# schema_final.net
KiCad netlist of a schematic drawn in EAGLE
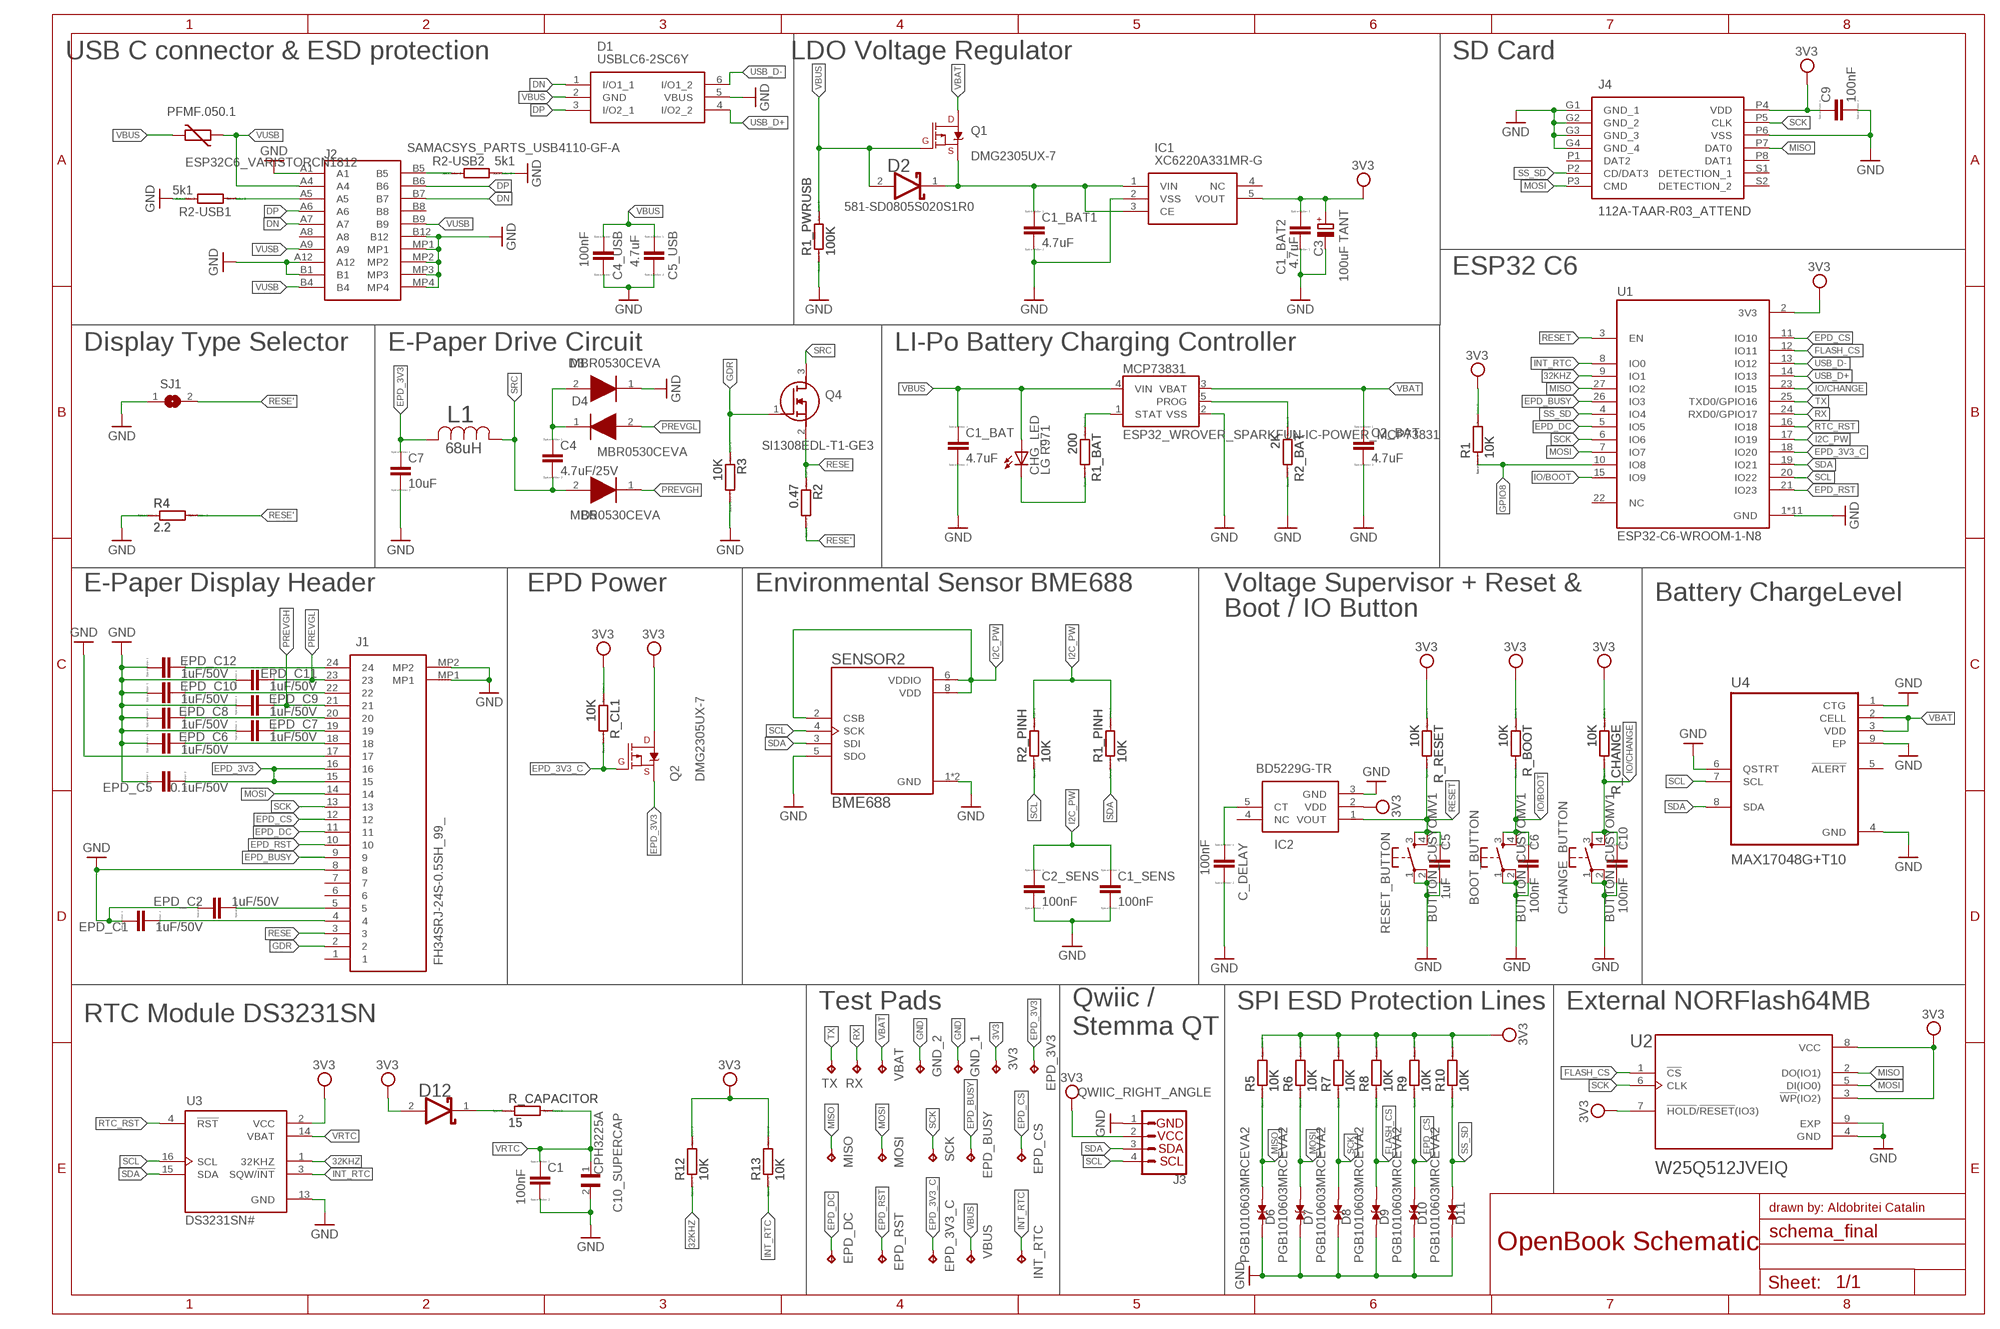
[diagram p0: schematic, sheet 1]

(export (version "E")
  (design (tool "Eeschema 10.0.6"))
  (components
    (comp (ref "3V3")
      (value "TP")
      (footprint "eagle-import:TP20R")
      (libsource (lib "eagle-import") (part "TP"))
    )
    (comp (ref "BOOT_BUTTON")
      (value "BUTTON_CUSYOMV1")
      (footprint "eagle-import:MYBUTTON")
      (libsource (lib "eagle-import") (part "BUTTON_CUSYOMV1"))
    )
    (comp (ref "C1")
      (value "100nF")
      (footprint "eagle-import:EAGLE-LTSPICE_C0402")
      (libsource (lib "eagle-import") (part "EAGLE-LTSPICE_C"))
    )
    (comp (ref "C1_BAT")
      (value "4.7uF")
      (footprint "eagle-import:EAGLE-LTSPICE_C0402")
      (libsource (lib "eagle-import") (part "EAGLE-LTSPICE_C"))
    )
    (comp (ref "C1_BAT1")
      (value "4.7uF")
      (footprint "eagle-import:EAGLE-LTSPICE_C0402")
      (libsource (lib "eagle-import") (part "EAGLE-LTSPICE_C"))
    )
    (comp (ref "C1_BAT2")
      (value "4.7uF")
      (footprint "eagle-import:EAGLE-LTSPICE_C0402")
      (libsource (lib "eagle-import") (part "EAGLE-LTSPICE_C"))
    )
    (comp (ref "C1_SENS")
      (value "100nF")
      (footprint "eagle-import:EAGLE-LTSPICE_C0402")
      (libsource (lib "eagle-import") (part "EAGLE-LTSPICE_C"))
    )
    (comp (ref "C2_BAT")
      (value "4.7uF")
      (footprint "eagle-import:EAGLE-LTSPICE_C0402")
      (libsource (lib "eagle-import") (part "EAGLE-LTSPICE_C"))
    )
    (comp (ref "C2_SENS")
      (value "100nF")
      (footprint "eagle-import:EAGLE-LTSPICE_C0402")
      (libsource (lib "eagle-import") (part "EAGLE-LTSPICE_C"))
    )
    (comp (ref "C3")
      (value "100uF TANT")
      (footprint "eagle-import:RCL_CT3528")
      (libsource (lib "eagle-import") (part "RCL_CPOL-EUCT3528"))
    )
    (comp (ref "C4")
      (value "4.7uF/25V")
      (footprint "eagle-import:EAGLE-LTSPICE_C0402")
      (libsource (lib "eagle-import") (part "EAGLE-LTSPICE_C"))
    )
    (comp (ref "C4_USB")
      (value "100nF")
      (footprint "eagle-import:EAGLE-LTSPICE_C0402")
      (libsource (lib "eagle-import") (part "EAGLE-LTSPICE_C"))
    )
    (comp (ref "C5")
      (value "1uF")
      (footprint "eagle-import:EAGLE-LTSPICE_C0402")
      (libsource (lib "eagle-import") (part "EAGLE-LTSPICE_C"))
    )
    (comp (ref "C5_USB")
      (value "4.7uF")
      (footprint "eagle-import:EAGLE-LTSPICE_C0402")
      (libsource (lib "eagle-import") (part "EAGLE-LTSPICE_C"))
    )
    (comp (ref "C6")
      (value "100nF")
      (footprint "eagle-import:EAGLE-LTSPICE_C0402")
      (libsource (lib "eagle-import") (part "EAGLE-LTSPICE_C"))
    )
    (comp (ref "C7")
      (value "10uF")
      (footprint "eagle-import:EAGLE-LTSPICE_C0402")
      (libsource (lib "eagle-import") (part "EAGLE-LTSPICE_C"))
    )
    (comp (ref "C9")
      (value "100nF")
      (footprint "eagle-import:EAGLE-LTSPICE_C0402")
      (libsource (lib "eagle-import") (part "EAGLE-LTSPICE_C"))
    )
    (comp (ref "C10")
      (value "100nF")
      (footprint "eagle-import:EAGLE-LTSPICE_C0402")
      (libsource (lib "eagle-import") (part "EAGLE-LTSPICE_C"))
    )
    (comp (ref "C10_SUPERCAP")
      (value "CPH3225A")
      (footprint "eagle-import:CAPCP3225X100N")
      (fields (field (name "MF") "Seiko Instruments"))
      (libsource (lib "eagle-import") (part "CPH3225A"))
    )
    (comp (ref "CHANGE_BUTTON")
      (value "BUTTON_CUSYOMV1")
      (footprint "eagle-import:MYBUTTON")
      (libsource (lib "eagle-import") (part "BUTTON_CUSYOMV1"))
    )
    (comp (ref "CHG_LED")
      (value "LG R971")
      (footprint "eagle-import:ADAFRUIT_CHIP-LED0603")
      (libsource (lib "eagle-import") (part "ADAFRUIT_LEDCHIP-LED0603"))
    )
    (comp (ref "C_DELAY")
      (value "100nF")
      (footprint "eagle-import:EAGLE-LTSPICE_C0402")
      (libsource (lib "eagle-import") (part "EAGLE-LTSPICE_C"))
    )
    (comp (ref "D1")
      (value "USBLC6-2SC6Y")
      (footprint "eagle-import:SOT95P280X145-6N")
      (fields (field (name "MF") "STMicroelectronics"))
      (libsource (lib "eagle-import") (part "USBLC6-2SC6Y"))
    )
    (comp (ref "D2")
      (value "ESP32_WROVER_AVX---SD0805S020S1R0_AVX_SD0805S020S1R0_0_0AVX_SD0805S020S1R0_0_0")
      (footprint "eagle-import:ESP32_WROVER_AVX---SD0805S020S1R0_AVX_SD0805S020S1R0_0")
      (fields
        (field (name "DIGIKEY_PART_NUMBER") "478-7800-1-ND")
        (field (name "MF") "AVX")
        (field (name "MOUSER_PART_NUMBER") "581-SD0805S020S1R0")
      )
      (libsource (lib "eagle-import") (part "ESP32_WROVER_AVX---SD0805S020S1R0_AVX_SD0805S020S1R0_0_0AVX_SD0805S020S1R0_0_0"))
    )
    (comp (ref "D3")
      (value "MBR0530CEVA")
      (footprint "eagle-import:SOD3716X135N")
      (libsource (lib "eagle-import") (part "MBR0530CEVA"))
    )
    (comp (ref "D4")
      (value "MBR0530CEVA")
      (footprint "eagle-import:SOD3716X135N")
      (libsource (lib "eagle-import") (part "MBR0530CEVA"))
    )
    (comp (ref "D5")
      (value "MBR0530CEVA")
      (footprint "eagle-import:SOD3716X135N")
      (libsource (lib "eagle-import") (part "MBR0530CEVA"))
    )
    (comp (ref "D6")
      (value "PGB1010603MRCEVA2")
      (footprint "eagle-import:DIOC1608X36N")
      (libsource (lib "eagle-import") (part "PGB1010603MRCEVA2"))
    )
    (comp (ref "D7")
      (value "PGB1010603MRCEVA2")
      (footprint "eagle-import:DIOC1608X36N")
      (libsource (lib "eagle-import") (part "PGB1010603MRCEVA2"))
    )
    (comp (ref "D8")
      (value "PGB1010603MRCEVA2")
      (footprint "eagle-import:DIOC1608X36N")
      (libsource (lib "eagle-import") (part "PGB1010603MRCEVA2"))
    )
    (comp (ref "D9")
      (value "PGB1010603MRCEVA2")
      (footprint "eagle-import:DIOC1608X36N")
      (libsource (lib "eagle-import") (part "PGB1010603MRCEVA2"))
    )
    (comp (ref "D10")
      (value "PGB1010603MRCEVA2")
      (footprint "eagle-import:DIOC1608X36N")
      (libsource (lib "eagle-import") (part "PGB1010603MRCEVA2"))
    )
    (comp (ref "D11")
      (value "PGB1010603MRCEVA2")
      (footprint "eagle-import:DIOC1608X36N")
      (libsource (lib "eagle-import") (part "PGB1010603MRCEVA2"))
    )
    (comp (ref "D12")
      (value "ESP32_WROVER_AVX---SD0805S020S1R0_AVX_SD0805S020S1R0_0_0AVX_SD0805S020S1R0_0_0")
      (footprint "eagle-import:ESP32_WROVER_AVX---SD0805S020S1R0_AVX_SD0805S020S1R0_0")
      (fields
        (field (name "DIGIKEY_PART_NUMBER") "478-7800-1-ND")
        (field (name "MF") "AVX")
        (field (name "MOUSER_PART_NUMBER") "581-SD0805S020S1R0")
      )
      (libsource (lib "eagle-import") (part "ESP32_WROVER_AVX---SD0805S020S1R0_AVX_SD0805S020S1R0_0_0AVX_SD0805S020S1R0_0_0"))
    )
    (comp (ref "EPD_3V3")
      (value "TP")
      (footprint "eagle-import:TP20R")
      (libsource (lib "eagle-import") (part "TP"))
    )
    (comp (ref "EPD_3V3_C")
      (value "TP")
      (footprint "eagle-import:TP20R")
      (libsource (lib "eagle-import") (part "TP"))
    )
    (comp (ref "EPD_BUSY")
      (value "TP")
      (footprint "eagle-import:TP20R")
      (libsource (lib "eagle-import") (part "TP"))
    )
    (comp (ref "EPD_C1")
      (value "1uF/50V")
      (footprint "eagle-import:EAGLE-LTSPICE_C0402")
      (libsource (lib "eagle-import") (part "EAGLE-LTSPICE_C"))
    )
    (comp (ref "EPD_C2")
      (value "1uF/50V")
      (footprint "eagle-import:EAGLE-LTSPICE_C0402")
      (libsource (lib "eagle-import") (part "EAGLE-LTSPICE_C"))
    )
    (comp (ref "EPD_C5")
      (value "0.1uF/50V")
      (footprint "eagle-import:EAGLE-LTSPICE_C0402")
      (libsource (lib "eagle-import") (part "EAGLE-LTSPICE_C"))
    )
    (comp (ref "EPD_C6")
      (value "1uF/50V")
      (footprint "eagle-import:EAGLE-LTSPICE_C0402")
      (libsource (lib "eagle-import") (part "EAGLE-LTSPICE_C"))
    )
    (comp (ref "EPD_C7")
      (value "1uF/50V")
      (footprint "eagle-import:EAGLE-LTSPICE_C0402")
      (libsource (lib "eagle-import") (part "EAGLE-LTSPICE_C"))
    )
    (comp (ref "EPD_C8")
      (value "1uF/50V")
      (footprint "eagle-import:EAGLE-LTSPICE_C0402")
      (libsource (lib "eagle-import") (part "EAGLE-LTSPICE_C"))
    )
    (comp (ref "EPD_C9")
      (value "1uF/50V")
      (footprint "eagle-import:EAGLE-LTSPICE_C0402")
      (libsource (lib "eagle-import") (part "EAGLE-LTSPICE_C"))
    )
    (comp (ref "EPD_C10")
      (value "1uF/50V")
      (footprint "eagle-import:EAGLE-LTSPICE_C0402")
      (libsource (lib "eagle-import") (part "EAGLE-LTSPICE_C"))
    )
    (comp (ref "EPD_C11")
      (value "1uF/50V")
      (footprint "eagle-import:EAGLE-LTSPICE_C0402")
      (libsource (lib "eagle-import") (part "EAGLE-LTSPICE_C"))
    )
    (comp (ref "EPD_C12")
      (value "1uF/50V")
      (footprint "eagle-import:EAGLE-LTSPICE_C0402")
      (libsource (lib "eagle-import") (part "EAGLE-LTSPICE_C"))
    )
    (comp (ref "EPD_CS")
      (value "TP")
      (footprint "eagle-import:TP20R")
      (libsource (lib "eagle-import") (part "TP"))
    )
    (comp (ref "EPD_DC")
      (value "TP")
      (footprint "eagle-import:TP20R")
      (libsource (lib "eagle-import") (part "TP"))
    )
    (comp (ref "EPD_RST")
      (value "TP")
      (footprint "eagle-import:TP20R")
      (libsource (lib "eagle-import") (part "TP"))
    )
    (comp (ref "GND_1")
      (value "TP")
      (footprint "eagle-import:TP20R")
      (libsource (lib "eagle-import") (part "TP"))
    )
    (comp (ref "GND_2")
      (value "TP")
      (footprint "eagle-import:TP20R")
      (libsource (lib "eagle-import") (part "TP"))
    )
    (comp (ref "IC1")
      (value "XC6220A331MR-G")
      (footprint "eagle-import:SOT95P280X120-5N")
      (fields (field (name "MOUSER_PART_NUMBER") "865-XC6220A331MR-G"))
      (libsource (lib "eagle-import") (part "XC6220A331MR-G"))
    )
    (comp (ref "IC2")
      (value "BD5229G-TR")
      (footprint "eagle-import:SOT95P280X125-5N")
      (fields (field (name "MOUSER_PART_NUMBER") "755-BD5229G-TR"))
      (libsource (lib "eagle-import") (part "BD5229G-TR"))
    )
    (comp (ref "INT_RTC")
      (value "TP")
      (footprint "eagle-import:TP20R")
      (libsource (lib "eagle-import") (part "TP"))
    )
    (comp (ref "J1")
      (value "FH34SRJ-24S-0.5SH_99_")
      (footprint "eagle-import:FH34SRJ24S05SH99")
      (fields
        (field (name "MANUFACTURER_PART_NUMBER") "FH34SRJ-24S-0.5SH(99)")
        (field (name "MOUSER_PART_NUMBER") "798-FH34SRJ24S05SH99")
      )
      (libsource (lib "eagle-import") (part "FH34SRJ-24S-0.5SH_99_"))
    )
    (comp (ref "J2")
      (value "SAMACSYS_PARTS_USB4110-GF-A")
      (footprint "eagle-import:SAMACSYS_PARTS_USB4110GFA")
      (fields
        (field (name "MANUFACTURER_PART_NUMBER") "USB4110-GF-A")
        (field (name "MOUSER_PART_NUMBER") "640-USB4110-GF-A")
      )
      (libsource (lib "eagle-import") (part "SAMACSYS_PARTS_USB4110-GF-A"))
    )
    (comp (ref "J3")
      (value "QWIIC_RIGHT_ANGLE")
      (footprint "eagle-import:JST04_1MM_RA")
      (libsource (lib "eagle-import") (part "QWIIC_CONNECTORJS-1MM"))
    )
    (comp (ref "J4")
      (value "112A-TAAR-R03_ATTEND")
      (footprint "eagle-import:112ATAARR03ATTEND")
      (fields (field (name "MANUFACTURER_PART_NUMBER") "112A-TAAR-R03 ATTEND"))
      (libsource (lib "eagle-import") (part "112A-TAAR-R03_ATTEND"))
    )
    (comp (ref "L1")
      (value "68uH")
      (footprint "eagle-import:IND_4828-WE-TPC_WRE")
      (fields
        (field (name "MANUFACTURER_PART_NUMBER") "744043680")
        (field (name "COPYRIGHT") "Copyright (C) 2024 Ultra Librarian. All rights reserved.")
      )
      (libsource (lib "eagle-import") (part "744043680IND_4828-WE-TPC_WRE"))
    )
    (comp (ref "MCP73831")
      (value "ESP32_WROVER_SPARKFUN-IC-POWER_MCP73831")
      (footprint "eagle-import:ESP32_WROVER_SPARKFUN-IC-POWER_SOT23-5")
      (libsource (lib "eagle-import") (part "ESP32_WROVER_SPARKFUN-IC-POWER_MCP73831"))
    )
    (comp (ref "MISO")
      (value "TP")
      (footprint "eagle-import:TP20R")
      (libsource (lib "eagle-import") (part "TP"))
    )
    (comp (ref "MOSI")
      (value "TP")
      (footprint "eagle-import:TP20R")
      (libsource (lib "eagle-import") (part "TP"))
    )
    (comp (ref "PFMF.050.1")
      (value "ESP32C6_VARISTORCN1812")
      (footprint "eagle-import:ESP32C6_VARISTOR_CT_CN1812")
      (libsource (lib "eagle-import") (part "ESP32C6_VARISTORCN1812"))
    )
    (comp (ref "Q1")
      (value "20V/4.2A/52mΩ/1.4W")
      (footprint "eagle-import:ESP32_WROVER_SPARKFUN-DISCRETESEMI_SOT23-3")
      (libsource (lib "eagle-import") (part "ESP32_WROVER_SPARKFUN-DISCRETESEMI_MOSFET_PCH"))
    )
    (comp (ref "Q2")
      (value "20V/4.2A/52mΩ/1.4W")
      (footprint "eagle-import:ESP32_WROVER_SPARKFUN-DISCRETESEMI_SOT23-3")
      (libsource (lib "eagle-import") (part "ESP32_WROVER_SPARKFUN-DISCRETESEMI_MOSFET_PCH"))
    )
    (comp (ref "Q4")
      (value "SI1308EDL-T1-GE3")
      (footprint "eagle-import:SOT65P210X110-3N")
      (fields (field (name "MF") "Vishay Siliconix"))
      (libsource (lib "eagle-import") (part "SI1308EDL-T1-GE3"))
    )
    (comp (ref "R1")
      (value "10K")
      (footprint "eagle-import:ESP32_WROVER_EAGLE-LTSPICE_R0402")
      (libsource (lib "eagle-import") (part "ESP32_WROVER_EAGLE-LTSPICE_R"))
    )
    (comp (ref "R1_BAT")
      (value "200")
      (footprint "eagle-import:ESP32_WROVER_EAGLE-LTSPICE_R0402")
      (libsource (lib "eagle-import") (part "ESP32_WROVER_EAGLE-LTSPICE_R"))
    )
    (comp (ref "R1_PINH")
      (value "10K")
      (footprint "eagle-import:ESP32_WROVER_EAGLE-LTSPICE_R0402")
      (libsource (lib "eagle-import") (part "ESP32_WROVER_EAGLE-LTSPICE_R"))
    )
    (comp (ref "R1_PWRUSB")
      (value "100K")
      (footprint "eagle-import:ESP32_WROVER_EAGLE-LTSPICE_R0402")
      (libsource (lib "eagle-import") (part "ESP32_WROVER_EAGLE-LTSPICE_R"))
    )
    (comp (ref "R2")
      (value "0.47")
      (footprint "eagle-import:ESP32_WROVER_EAGLE-LTSPICE_R0402")
      (libsource (lib "eagle-import") (part "ESP32_WROVER_EAGLE-LTSPICE_R"))
    )
    (comp (ref "R2-USB1")
      (value "5k1")
      (footprint "eagle-import:ESP32_WROVER_EAGLE-LTSPICE_R0402")
      (libsource (lib "eagle-import") (part "ESP32_WROVER_EAGLE-LTSPICE_R"))
    )
    (comp (ref "R2-USB2")
      (value "5k1")
      (footprint "eagle-import:ESP32_WROVER_EAGLE-LTSPICE_R0402")
      (libsource (lib "eagle-import") (part "ESP32_WROVER_EAGLE-LTSPICE_R"))
    )
    (comp (ref "R2_BAT")
      (value "2K")
      (footprint "eagle-import:ESP32_WROVER_EAGLE-LTSPICE_R0402")
      (libsource (lib "eagle-import") (part "ESP32_WROVER_EAGLE-LTSPICE_R"))
    )
    (comp (ref "R2_PINH")
      (value "10K")
      (footprint "eagle-import:ESP32_WROVER_EAGLE-LTSPICE_R0402")
      (libsource (lib "eagle-import") (part "ESP32_WROVER_EAGLE-LTSPICE_R"))
    )
    (comp (ref "R3")
      (value "10K")
      (footprint "eagle-import:ESP32_WROVER_EAGLE-LTSPICE_R0402")
      (libsource (lib "eagle-import") (part "ESP32_WROVER_EAGLE-LTSPICE_R"))
    )
    (comp (ref "R4")
      (value "2.2")
      (footprint "eagle-import:ESP32_WROVER_EAGLE-LTSPICE_R0402")
      (libsource (lib "eagle-import") (part "ESP32_WROVER_EAGLE-LTSPICE_R"))
    )
    (comp (ref "R5")
      (value "10K")
      (footprint "eagle-import:ESP32_WROVER_EAGLE-LTSPICE_R0402")
      (libsource (lib "eagle-import") (part "ESP32_WROVER_EAGLE-LTSPICE_R"))
    )
    (comp (ref "R6")
      (value "10K")
      (footprint "eagle-import:ESP32_WROVER_EAGLE-LTSPICE_R0402")
      (libsource (lib "eagle-import") (part "ESP32_WROVER_EAGLE-LTSPICE_R"))
    )
    (comp (ref "R7")
      (value "10K")
      (footprint "eagle-import:ESP32_WROVER_EAGLE-LTSPICE_R0402")
      (libsource (lib "eagle-import") (part "ESP32_WROVER_EAGLE-LTSPICE_R"))
    )
    (comp (ref "R8")
      (value "10K")
      (footprint "eagle-import:ESP32_WROVER_EAGLE-LTSPICE_R0402")
      (libsource (lib "eagle-import") (part "ESP32_WROVER_EAGLE-LTSPICE_R"))
    )
    (comp (ref "R9")
      (value "10K")
      (footprint "eagle-import:ESP32_WROVER_EAGLE-LTSPICE_R0402")
      (libsource (lib "eagle-import") (part "ESP32_WROVER_EAGLE-LTSPICE_R"))
    )
    (comp (ref "R10")
      (value "10K")
      (footprint "eagle-import:ESP32_WROVER_EAGLE-LTSPICE_R0402")
      (libsource (lib "eagle-import") (part "ESP32_WROVER_EAGLE-LTSPICE_R"))
    )
    (comp (ref "R12")
      (value "10K")
      (footprint "eagle-import:ESP32_WROVER_EAGLE-LTSPICE_R0402")
      (libsource (lib "eagle-import") (part "ESP32_WROVER_EAGLE-LTSPICE_R"))
    )
    (comp (ref "R13")
      (value "10K")
      (footprint "eagle-import:ESP32_WROVER_EAGLE-LTSPICE_R0402")
      (libsource (lib "eagle-import") (part "ESP32_WROVER_EAGLE-LTSPICE_R"))
    )
    (comp (ref "RESET_BUTTON")
      (value "BUTTON_CUSYOMV1")
      (footprint "eagle-import:MYBUTTON")
      (libsource (lib "eagle-import") (part "BUTTON_CUSYOMV1"))
    )
    (comp (ref "RX")
      (value "TP")
      (footprint "eagle-import:TP20R")
      (libsource (lib "eagle-import") (part "TP"))
    )
    (comp (ref "R_BOOT")
      (value "10K")
      (footprint "eagle-import:ESP32_WROVER_EAGLE-LTSPICE_R0402")
      (libsource (lib "eagle-import") (part "ESP32_WROVER_EAGLE-LTSPICE_R"))
    )
    (comp (ref "R_CAPACITOR")
      (value "15")
      (footprint "eagle-import:ESP32_WROVER_EAGLE-LTSPICE_R0402")
      (libsource (lib "eagle-import") (part "ESP32_WROVER_EAGLE-LTSPICE_R"))
    )
    (comp (ref "R_CHANGE")
      (value "10K")
      (footprint "eagle-import:ESP32_WROVER_EAGLE-LTSPICE_R0402")
      (libsource (lib "eagle-import") (part "ESP32_WROVER_EAGLE-LTSPICE_R"))
    )
    (comp (ref "R_CL1")
      (value "10K")
      (footprint "eagle-import:ESP32_WROVER_EAGLE-LTSPICE_R0402")
      (libsource (lib "eagle-import") (part "ESP32_WROVER_EAGLE-LTSPICE_R"))
    )
    (comp (ref "R_RESET")
      (value "10K")
      (footprint "eagle-import:ESP32_WROVER_EAGLE-LTSPICE_R0402")
      (libsource (lib "eagle-import") (part "ESP32_WROVER_EAGLE-LTSPICE_R"))
    )
    (comp (ref "SCK")
      (value "TP")
      (footprint "eagle-import:TP20R")
      (libsource (lib "eagle-import") (part "TP"))
    )
    (comp (ref "SENSOR2")
      (value "BME688")
      (footprint "eagle-import:ESP32_WROVER_BME680_PSON80P300X300X100-8N")
      (fields (field (name "MF") "Bosch Sensortec") (field (name "MP") "BME680"))
      (libsource (lib "eagle-import") (part "ESP32_WROVER_BME680_BME680"))
    )
    (comp (ref "SJ1") (value "SJ") (footprint "eagle-import:SJ") (libsource (lib "eagle-import") (part "SJ")))
    (comp (ref "TX")
      (value "TP")
      (footprint "eagle-import:TP20R")
      (libsource (lib "eagle-import") (part "TP"))
    )
    (comp (ref "U1")
      (value "ESP32-C6-WROOM-1-N8")
      (footprint "eagle-import:XCVR_ESP32-C6-WROOM-1-N8")
      (fields (field (name "MF") "Espressif Systems"))
      (libsource (lib "eagle-import") (part "ESP32-C6-WROOM-1-N8"))
    )
    (comp (ref "U2")
      (value "W25Q512JVEIQ")
      (footprint "eagle-import:SON127P600X800X80-9N")
      (fields (field (name "MF") "Winbond Electronics"))
      (libsource (lib "eagle-import") (part "W25Q512JVEIQ"))
    )
    (comp (ref "U3")
      (value "DS3231SN#")
      (footprint "eagle-import:SOIC127P1032X265-16N")
      (fields (field (name "MF") "Analog Devices"))
      (libsource (lib "eagle-import") (part "DS3231SN#"))
    )
    (comp (ref "U4")
      (value "MAX17048G+T10")
      (footprint "eagle-import:SON50P200X200X80-9N")
      (fields (field (name "MF") "Analog Devices"))
      (libsource (lib "eagle-import") (part "MAX17048G+T10"))
    )
    (comp (ref "VBAT")
      (value "TP")
      (footprint "eagle-import:TP20R")
      (libsource (lib "eagle-import") (part "TP"))
    )
    (comp (ref "VBUS")
      (value "TP")
      (footprint "eagle-import:TP20R")
      (libsource (lib "eagle-import") (part "TP"))
    )
  )
  (nets
    (net (code "1") (name "3V3") (class "Default")
      (node (ref "3V3") (pin "TP") (pinfunction "TP_TP") (pintype "input"))
      (node (ref "C1_BAT2") (pin "2") (pinfunction "2_2") (pintype "passive"))
      (node (ref "C3") (pin "+") (pinfunction "+_+") (pintype "passive"))
      (node (ref "C9") (pin "1") (pinfunction "1_1") (pintype "passive"))
      (node (ref "D12") (pin "2") (pinfunction "ANODE_2") (pintype "bidirectional"))
      (node (ref "IC1") (pin "5") (pinfunction "VOUT_5") (pintype "bidirectional"))
      (node (ref "IC2") (pin "2") (pinfunction "VDD_2") (pintype "bidirectional"))
      (node (ref "J3") (pin "2") (pinfunction "2_2") (pintype "power_in"))
      (node (ref "J4") (pin "P4") (pinfunction "VDD_P4") (pintype "bidirectional"))
      (node (ref "Q2") (pin "3") (pinfunction "D_3") (pintype "bidirectional"))
      (node (ref "R1") (pin "2") (pinfunction "2_2") (pintype "passive"))
      (node (ref "R10") (pin "2") (pinfunction "2_2") (pintype "passive"))
      (node (ref "R12") (pin "2") (pinfunction "2_2") (pintype "passive"))
      (node (ref "R13") (pin "2") (pinfunction "2_2") (pintype "passive"))
      (node (ref "R5") (pin "2") (pinfunction "2_2") (pintype "passive"))
      (node (ref "R6") (pin "2") (pinfunction "2_2") (pintype "passive"))
      (node (ref "R7") (pin "2") (pinfunction "2_2") (pintype "passive"))
      (node (ref "R8") (pin "2") (pinfunction "2_2") (pintype "passive"))
      (node (ref "R9") (pin "2") (pinfunction "2_2") (pintype "passive"))
      (node (ref "R_BOOT") (pin "1") (pinfunction "1_1") (pintype "passive"))
      (node (ref "R_CHANGE") (pin "1") (pinfunction "1_1") (pintype "passive"))
      (node (ref "R_CL1") (pin "1") (pinfunction "1_1") (pintype "passive"))
      (node (ref "R_RESET") (pin "1") (pinfunction "1_1") (pintype "passive"))
      (node (ref "U1") (pin "2") (pinfunction "3V3_2") (pintype "power_in"))
      (node (ref "U2") (pin "3") (pinfunction "~{WP}(IO2)_3") (pintype "bidirectional"))
      (node (ref "U2") (pin "7") (pinfunction "~{HOLD}/~{RESET}(IO3)_7") (pintype "bidirectional"))
      (node (ref "U2") (pin "8") (pinfunction "VCC_8") (pintype "power_in"))
      (node (ref "U3") (pin "2") (pinfunction "VCC_2") (pintype "power_in"))
    )
    (net (code "2") (name "32KHZ") (class "Default")
      (node (ref "R12") (pin "1") (pinfunction "1_1") (pintype "passive"))
      (node (ref "U1") (pin "9") (pinfunction "IO1_9") (pintype "bidirectional"))
      (node (ref "U3") (pin "1") (pinfunction "32KHZ_1") (pintype "output"))
    )
    (net (code "3") (name "DN") (class "Default")
      (node (ref "D1") (pin "1") (pinfunction "I/O1_1_1") (pintype "bidirectional"))
      (node (ref "J2") (pin "A7") (pinfunction "A7_A7") (pintype "bidirectional"))
      (node (ref "J2") (pin "B7") (pinfunction "B7_B7") (pintype "bidirectional"))
    )
    (net (code "4") (name "DP") (class "Default")
      (node (ref "D1") (pin "3") (pinfunction "I/O2_1_3") (pintype "bidirectional"))
      (node (ref "J2") (pin "A6") (pinfunction "A6_A6") (pintype "bidirectional"))
      (node (ref "J2") (pin "B6") (pinfunction "B6_B6") (pintype "bidirectional"))
    )
    (net (code "5") (name "EPD_3V3") (class "Default")
      (node (ref "C7") (pin "1") (pinfunction "1_1") (pintype "passive"))
      (node (ref "EPD_3V3") (pin "TP") (pinfunction "TP_TP") (pintype "input"))
      (node (ref "EPD_C5") (pin "2") (pinfunction "2_2") (pintype "passive"))
      (node (ref "J1") (pin "15") (pinfunction "15_15") (pintype "bidirectional"))
      (node (ref "J1") (pin "16") (pinfunction "16_16") (pintype "bidirectional"))
      (node (ref "L1") (pin "2") (pinfunction "2_2") (pintype "passive"))
      (node (ref "Q2") (pin "2") (pinfunction "S_2") (pintype "bidirectional"))
    )
    (net (code "6") (name "EPD_3V3_C") (class "Default")
      (node (ref "EPD_3V3_C") (pin "TP") (pinfunction "TP_TP") (pintype "input"))
      (node (ref "Q2") (pin "1") (pinfunction "G_1") (pintype "bidirectional"))
      (node (ref "R_CL1") (pin "2") (pinfunction "2_2") (pintype "passive"))
      (node (ref "U1") (pin "18") (pinfunction "IO20_18") (pintype "bidirectional"))
    )
    (net (code "7") (name "EPD_BUSY") (class "Default")
      (node (ref "EPD_BUSY") (pin "TP") (pinfunction "TP_TP") (pintype "input"))
      (node (ref "J1") (pin "9") (pinfunction "9_9") (pintype "bidirectional"))
      (node (ref "U1") (pin "26") (pinfunction "IO3_26") (pintype "bidirectional"))
    )
    (net (code "8") (name "EPD_CS") (class "Default")
      (node (ref "D10") (pin "2") (pinfunction "2_2") (pintype "passive"))
      (node (ref "EPD_CS") (pin "TP") (pinfunction "TP_TP") (pintype "input"))
      (node (ref "J1") (pin "12") (pinfunction "12_12") (pintype "bidirectional"))
      (node (ref "R9") (pin "1") (pinfunction "1_1") (pintype "passive"))
      (node (ref "U1") (pin "11") (pinfunction "IO10_11") (pintype "bidirectional"))
    )
    (net (code "9") (name "EPD_DC") (class "Default")
      (node (ref "EPD_DC") (pin "TP") (pinfunction "TP_TP") (pintype "input"))
      (node (ref "J1") (pin "11") (pinfunction "11_11") (pintype "bidirectional"))
      (node (ref "U1") (pin "5") (pinfunction "IO5_5") (pintype "bidirectional"))
    )
    (net (code "10") (name "EPD_RST") (class "Default")
      (node (ref "EPD_RST") (pin "TP") (pinfunction "TP_TP") (pintype "input"))
      (node (ref "J1") (pin "10") (pinfunction "10_10") (pintype "bidirectional"))
      (node (ref "U1") (pin "21") (pinfunction "IO23_21") (pintype "bidirectional"))
    )
    (net (code "11") (name "FLASH_CS") (class "Default")
      (node (ref "D9") (pin "2") (pinfunction "2_2") (pintype "passive"))
      (node (ref "R8") (pin "1") (pinfunction "1_1") (pintype "passive"))
      (node (ref "U1") (pin "12") (pinfunction "IO11_12") (pintype "bidirectional"))
      (node (ref "U2") (pin "1") (pinfunction "~{CS}_1") (pintype "input"))
    )
    (net (code "12") (name "GDR") (class "Default")
      (node (ref "J1") (pin "2") (pinfunction "2_2") (pintype "bidirectional"))
      (node (ref "Q4") (pin "1") (pinfunction "G_1") (pintype "bidirectional"))
      (node (ref "R3") (pin "1") (pinfunction "1_1") (pintype "passive"))
    )
    (net (code "13") (name "GND") (class "Default")
      (node (ref "BOOT_BUTTON") (pin "1") (pinfunction "1_1") (pintype "passive"))
      (node (ref "BOOT_BUTTON") (pin "2") (pinfunction "2_2") (pintype "passive"))
      (node (ref "C1") (pin "2") (pinfunction "2_2") (pintype "passive"))
      (node (ref "C10") (pin "2") (pinfunction "2_2") (pintype "passive"))
      (node (ref "C10_SUPERCAP") (pin "2") (pinfunction "2_2") (pintype "passive"))
      (node (ref "C1_BAT") (pin "2") (pinfunction "2_2") (pintype "passive"))
      (node (ref "C1_BAT1") (pin "2") (pinfunction "2_2") (pintype "passive"))
      (node (ref "C1_BAT2") (pin "1") (pinfunction "1_1") (pintype "passive"))
      (node (ref "C1_SENS") (pin "2") (pinfunction "2_2") (pintype "passive"))
      (node (ref "C2_BAT") (pin "2") (pinfunction "2_2") (pintype "passive"))
      (node (ref "C2_SENS") (pin "2") (pinfunction "2_2") (pintype "passive"))
      (node (ref "C3") (pin "-") (pinfunction "-_-") (pintype "passive"))
      (node (ref "C4_USB") (pin "2") (pinfunction "2_2") (pintype "passive"))
      (node (ref "C5") (pin "2") (pinfunction "2_2") (pintype "passive"))
      (node (ref "C5_USB") (pin "2") (pinfunction "2_2") (pintype "passive"))
      (node (ref "C6") (pin "2") (pinfunction "2_2") (pintype "passive"))
      (node (ref "C7") (pin "2") (pinfunction "2_2") (pintype "passive"))
      (node (ref "C9") (pin "2") (pinfunction "2_2") (pintype "passive"))
      (node (ref "CHANGE_BUTTON") (pin "1") (pinfunction "1_1") (pintype "passive"))
      (node (ref "CHANGE_BUTTON") (pin "2") (pinfunction "2_2") (pintype "passive"))
      (node (ref "C_DELAY") (pin "2") (pinfunction "2_2") (pintype "passive"))
      (node (ref "D1") (pin "5") (pinfunction "VBUS_5") (pintype "bidirectional"))
      (node (ref "D10") (pin "1") (pinfunction "1_1") (pintype "passive"))
      (node (ref "D11") (pin "1") (pinfunction "1_1") (pintype "passive"))
      (node (ref "D3") (pin "1") (pinfunction "K_1") (pintype "bidirectional"))
      (node (ref "D6") (pin "1") (pinfunction "1_1") (pintype "passive"))
      (node (ref "D7") (pin "1") (pinfunction "1_1") (pintype "passive"))
      (node (ref "D8") (pin "1") (pinfunction "1_1") (pintype "passive"))
      (node (ref "D9") (pin "1") (pinfunction "1_1") (pintype "passive"))
      (node (ref "EPD_C1") (pin "1") (pinfunction "1_1") (pintype "passive"))
      (node (ref "EPD_C10") (pin "1") (pinfunction "1_1") (pintype "passive"))
      (node (ref "EPD_C11") (pin "1") (pinfunction "1_1") (pintype "passive"))
      (node (ref "EPD_C12") (pin "1") (pinfunction "1_1") (pintype "passive"))
      (node (ref "EPD_C2") (pin "1") (pinfunction "1_1") (pintype "passive"))
      (node (ref "EPD_C5") (pin "1") (pinfunction "1_1") (pintype "passive"))
      (node (ref "EPD_C6") (pin "1") (pinfunction "1_1") (pintype "passive"))
      (node (ref "EPD_C7") (pin "1") (pinfunction "1_1") (pintype "passive"))
      (node (ref "EPD_C8") (pin "1") (pinfunction "1_1") (pintype "passive"))
      (node (ref "EPD_C9") (pin "1") (pinfunction "1_1") (pintype "passive"))
      (node (ref "GND_1") (pin "TP") (pinfunction "TP_TP") (pintype "input"))
      (node (ref "GND_2") (pin "TP") (pinfunction "TP_TP") (pintype "input"))
      (node (ref "IC1") (pin "2") (pinfunction "VSS_2") (pintype "bidirectional"))
      (node (ref "IC2") (pin "3") (pinfunction "GND_3") (pintype "bidirectional"))
      (node (ref "J1") (pin "17") (pinfunction "17_17") (pintype "bidirectional"))
      (node (ref "J1") (pin "8") (pinfunction "8_8") (pintype "bidirectional"))
      (node (ref "J1") (pin "MP1") (pinfunction "MP1_MP1") (pintype "bidirectional"))
      (node (ref "J1") (pin "MP2") (pinfunction "MP2_MP2") (pintype "bidirectional"))
      (node (ref "J2") (pin "A1") (pinfunction "A1_A1") (pintype "bidirectional"))
      (node (ref "J2") (pin "A12") (pinfunction "A12_A12") (pintype "bidirectional"))
      (node (ref "J2") (pin "B1") (pinfunction "B1_B1") (pintype "bidirectional"))
      (node (ref "J2") (pin "B12") (pinfunction "B12_B12") (pintype "bidirectional"))
      (node (ref "J2") (pin "MP1") (pinfunction "MP1_MP1") (pintype "bidirectional"))
      (node (ref "J2") (pin "MP2") (pinfunction "MP2_MP2") (pintype "bidirectional"))
      (node (ref "J2") (pin "MP3") (pinfunction "MP3_MP3") (pintype "bidirectional"))
      (node (ref "J2") (pin "MP4") (pinfunction "MP4_MP4") (pintype "bidirectional"))
      (node (ref "J3") (pin "1") (pinfunction "1_1") (pintype "power_in"))
      (node (ref "J4") (pin "G1") (pinfunction "GND_1_G1") (pintype "bidirectional"))
      (node (ref "J4") (pin "G2") (pinfunction "GND_2_G2") (pintype "bidirectional"))
      (node (ref "J4") (pin "G3") (pinfunction "GND_3_G3") (pintype "bidirectional"))
      (node (ref "J4") (pin "G4") (pinfunction "GND_4_G4") (pintype "bidirectional"))
      (node (ref "J4") (pin "P6") (pinfunction "VSS_P6") (pintype "bidirectional"))
      (node (ref "MCP73831") (pin "2") (pinfunction "VSS_2") (pintype "power_in"))
      (node (ref "R1_PWRUSB") (pin "1") (pinfunction "1_1") (pintype "passive"))
      (node (ref "R2-USB1") (pin "1") (pinfunction "1_1") (pintype "passive"))
      (node (ref "R2-USB2") (pin "2") (pinfunction "2_2") (pintype "passive"))
      (node (ref "R2_BAT") (pin "2") (pinfunction "2_2") (pintype "passive"))
      (node (ref "R3") (pin "2") (pinfunction "2_2") (pintype "passive"))
      (node (ref "R4") (pin "1") (pinfunction "1_1") (pintype "passive"))
      (node (ref "RESET_BUTTON") (pin "1") (pinfunction "1_1") (pintype "passive"))
      (node (ref "RESET_BUTTON") (pin "2") (pinfunction "2_2") (pintype "passive"))
      (node (ref "SENSOR2") (pin "1") (pinfunction "GND_1") (pintype "power_in"))
      (node (ref "SENSOR2") (pin "5") (pinfunction "SDO_5") (pintype "bidirectional"))
      (node (ref "SENSOR2") (pin "7") (pinfunction "GND_7") (pintype "power_in"))
      (node (ref "SJ1") (pin "1") (pinfunction "1_1") (pintype "passive"))
      (node (ref "U1") (pin "1") (pinfunction "GND_1") (pintype "power_in"))
      (node (ref "U1") (pin "28") (pinfunction "GND_28") (pintype "power_in"))
      (node (ref "U1") (pin "29_1") (pinfunction "GND_29_1") (pintype "power_in"))
      (node (ref "U1") (pin "29_2") (pinfunction "GND_29_2") (pintype "power_in"))
      (node (ref "U1") (pin "29_3") (pinfunction "GND_29_3") (pintype "power_in"))
      (node (ref "U1") (pin "29_4") (pinfunction "GND_29_4") (pintype "power_in"))
      (node (ref "U1") (pin "29_5") (pinfunction "GND_29_5") (pintype "power_in"))
      (node (ref "U1") (pin "29_6") (pinfunction "GND_29_6") (pintype "power_in"))
      (node (ref "U1") (pin "29_7") (pinfunction "GND_29_7") (pintype "power_in"))
      (node (ref "U1") (pin "29_8") (pinfunction "GND_29_8") (pintype "power_in"))
      (node (ref "U1") (pin "29_9") (pinfunction "GND_29_9") (pintype "power_in"))
      (node (ref "U2") (pin "4") (pinfunction "GND_4") (pintype "power_in"))
      (node (ref "U2") (pin "9") (pinfunction "EXP_9") (pintype "passive"))
      (node (ref "U3") (pin "13") (pinfunction "GND_13") (pintype "power_in"))
      (node (ref "U4") (pin "1") (pinfunction "CTG_1") (pintype "power_in"))
      (node (ref "U4") (pin "4") (pinfunction "GND_4") (pintype "power_in"))
      (node (ref "U4") (pin "6") (pinfunction "QSTRT_6") (pintype "input"))
      (node (ref "U4") (pin "9") (pinfunction "EP_9") (pintype "power_in"))
    )
    (net (code "14") (name "GPIO8") (class "Default")
      (node (ref "R1") (pin "1") (pinfunction "1_1") (pintype "passive"))
      (node (ref "U1") (pin "10") (pinfunction "IO8_10") (pintype "bidirectional"))
    )
    (net (code "15") (name "I2C_PW") (class "Default")
      (node (ref "C1_SENS") (pin "1") (pinfunction "1_1") (pintype "passive"))
      (node (ref "C2_SENS") (pin "1") (pinfunction "1_1") (pintype "passive"))
      (node (ref "R1_PINH") (pin "2") (pinfunction "2_2") (pintype "passive"))
      (node (ref "R2_PINH") (pin "2") (pinfunction "2_2") (pintype "passive"))
      (node (ref "SENSOR2") (pin "2") (pinfunction "CSB_2") (pintype "input"))
      (node (ref "SENSOR2") (pin "6") (pinfunction "VDDIO_6") (pintype "power_in"))
      (node (ref "SENSOR2") (pin "8") (pinfunction "VDD_8") (pintype "power_in"))
      (node (ref "U1") (pin "17") (pinfunction "IO19_17") (pintype "bidirectional"))
    )
    (net (code "16") (name "INT_RTC") (class "Default")
      (node (ref "INT_RTC") (pin "TP") (pinfunction "TP_TP") (pintype "input"))
      (node (ref "R13") (pin "1") (pinfunction "1_1") (pintype "passive"))
      (node (ref "U1") (pin "8") (pinfunction "IO0_8") (pintype "bidirectional"))
      (node (ref "U3") (pin "3") (pinfunction "SQW/~{INT}_3") (pintype "output"))
    )
    (net (code "17") (name "IO{slash}BOOT") (class "Default")
      (node (ref "BOOT_BUTTON") (pin "3") (pinfunction "3_3") (pintype "passive"))
      (node (ref "BOOT_BUTTON") (pin "4") (pinfunction "4_4") (pintype "passive"))
      (node (ref "C6") (pin "1") (pinfunction "1_1") (pintype "passive"))
      (node (ref "R_BOOT") (pin "2") (pinfunction "2_2") (pintype "passive"))
      (node (ref "U1") (pin "15") (pinfunction "IO9_15") (pintype "bidirectional"))
    )
    (net (code "18") (name "IO{slash}CHANGE") (class "Default")
      (node (ref "C10") (pin "1") (pinfunction "1_1") (pintype "passive"))
      (node (ref "CHANGE_BUTTON") (pin "3") (pinfunction "3_3") (pintype "passive"))
      (node (ref "CHANGE_BUTTON") (pin "4") (pinfunction "4_4") (pintype "passive"))
      (node (ref "R_CHANGE") (pin "2") (pinfunction "2_2") (pintype "passive"))
      (node (ref "U1") (pin "23") (pinfunction "IO15_23") (pintype "bidirectional"))
    )
    (net (code "19") (name "MISO") (class "Default")
      (node (ref "D6") (pin "2") (pinfunction "2_2") (pintype "passive"))
      (node (ref "J4") (pin "P7") (pinfunction "DAT0_P7") (pintype "bidirectional"))
      (node (ref "MISO") (pin "TP") (pinfunction "TP_TP") (pintype "input"))
      (node (ref "R5") (pin "1") (pinfunction "1_1") (pintype "passive"))
      (node (ref "U1") (pin "27") (pinfunction "IO2_27") (pintype "bidirectional"))
      (node (ref "U2") (pin "2") (pinfunction "DO(IO1)_2") (pintype "bidirectional"))
    )
    (net (code "20") (name "MOSI") (class "Default")
      (node (ref "D7") (pin "2") (pinfunction "2_2") (pintype "passive"))
      (node (ref "J1") (pin "14") (pinfunction "14_14") (pintype "bidirectional"))
      (node (ref "J4") (pin "P3") (pinfunction "CMD_P3") (pintype "bidirectional"))
      (node (ref "MOSI") (pin "TP") (pinfunction "TP_TP") (pintype "input"))
      (node (ref "R6") (pin "1") (pinfunction "1_1") (pintype "passive"))
      (node (ref "U1") (pin "7") (pinfunction "IO7_7") (pintype "bidirectional"))
      (node (ref "U2") (pin "5") (pinfunction "DI(IO0)_5") (pintype "bidirectional"))
    )
    (net (code "21") (name "Net-(CHG_LED-PadC)") (class "Default")
      (node (ref "CHG_LED") (pin "C") (pinfunction "C_C") (pintype "passive"))
      (node (ref "R1_BAT") (pin "2") (pinfunction "2_2") (pintype "passive"))
    )
    (net (code "22") (name "Net-(D2-CATHODE)") (class "Default")
      (node (ref "C1_BAT1") (pin "1") (pinfunction "1_1") (pintype "passive"))
      (node (ref "D2") (pin "1") (pinfunction "CATHODE_1") (pintype "bidirectional"))
      (node (ref "IC1") (pin "1") (pinfunction "VIN_1") (pintype "bidirectional"))
      (node (ref "IC1") (pin "3") (pinfunction "CE_3") (pintype "bidirectional"))
      (node (ref "Q1") (pin "2") (pinfunction "S_2") (pintype "bidirectional"))
    )
    (net (code "23") (name "Net-(D3-A)") (class "Default")
      (node (ref "C4") (pin "1") (pinfunction "1_1") (pintype "passive"))
      (node (ref "D3") (pin "2") (pinfunction "A_2") (pintype "bidirectional"))
      (node (ref "D4") (pin "1") (pinfunction "K_1") (pintype "bidirectional"))
    )
    (net (code "24") (name "Net-(D12-CATHODE)") (class "Default")
      (node (ref "D12") (pin "1") (pinfunction "CATHODE_1") (pintype "bidirectional"))
      (node (ref "R_CAPACITOR") (pin "1") (pinfunction "1_1") (pintype "passive"))
    )
    (net (code "25") (name "Net-(EPD_C1-Pad2)") (class "Default")
      (node (ref "EPD_C1") (pin "2") (pinfunction "2_2") (pintype "passive"))
      (node (ref "J1") (pin "4") (pinfunction "4_4") (pintype "bidirectional"))
    )
    (net (code "26") (name "Net-(EPD_C2-Pad2)") (class "Default")
      (node (ref "EPD_C2") (pin "2") (pinfunction "2_2") (pintype "passive"))
      (node (ref "J1") (pin "5") (pinfunction "5_5") (pintype "bidirectional"))
    )
    (net (code "27") (name "Net-(EPD_C6-Pad2)") (class "Default")
      (node (ref "EPD_C6") (pin "2") (pinfunction "2_2") (pintype "passive"))
      (node (ref "J1") (pin "18") (pinfunction "18_18") (pintype "bidirectional"))
    )
    (net (code "28") (name "Net-(EPD_C7-Pad2)") (class "Default")
      (node (ref "EPD_C7") (pin "2") (pinfunction "2_2") (pintype "passive"))
      (node (ref "J1") (pin "19") (pinfunction "19_19") (pintype "bidirectional"))
    )
    (net (code "29") (name "Net-(EPD_C8-Pad2)") (class "Default")
      (node (ref "EPD_C8") (pin "2") (pinfunction "2_2") (pintype "passive"))
      (node (ref "J1") (pin "20") (pinfunction "20_20") (pintype "bidirectional"))
    )
    (net (code "30") (name "Net-(EPD_C10-Pad2)") (class "Default")
      (node (ref "EPD_C10") (pin "2") (pinfunction "2_2") (pintype "passive"))
      (node (ref "J1") (pin "22") (pinfunction "22_22") (pintype "bidirectional"))
    )
    (net (code "31") (name "Net-(EPD_C12-Pad2)") (class "Default")
      (node (ref "EPD_C12") (pin "2") (pinfunction "2_2") (pintype "passive"))
      (node (ref "J1") (pin "24") (pinfunction "24_24") (pintype "bidirectional"))
    )
    (net (code "32") (name "Net-(IC2-CT)") (class "Default")
      (node (ref "C_DELAY") (pin "1") (pinfunction "1_1") (pintype "passive"))
      (node (ref "IC2") (pin "5") (pinfunction "CT_5") (pintype "bidirectional"))
    )
    (net (code "33") (name "Net-(J2-PadA5)") (class "Default")
      (node (ref "J2") (pin "A5") (pinfunction "A5_A5") (pintype "bidirectional"))
      (node (ref "R2-USB1") (pin "2") (pinfunction "2_2") (pintype "passive"))
    )
    (net (code "34") (name "Net-(J2-PadB5)") (class "Default")
      (node (ref "J2") (pin "B5") (pinfunction "B5_B5") (pintype "bidirectional"))
      (node (ref "R2-USB2") (pin "1") (pinfunction "1_1") (pintype "passive"))
    )
    (net (code "35") (name "Net-(MCP73831-PROG)") (class "Default")
      (node (ref "MCP73831") (pin "5") (pinfunction "PROG_5") (pintype "input"))
      (node (ref "R2_BAT") (pin "1") (pinfunction "1_1") (pintype "passive"))
    )
    (net (code "36") (name "Net-(MCP73831-STAT)") (class "Default")
      (node (ref "MCP73831") (pin "1") (pinfunction "STAT_1") (pintype "output"))
      (node (ref "R1_BAT") (pin "1") (pinfunction "1_1") (pintype "passive"))
    )
    (net (code "37") (name "PREVGH") (class "Default")
      (node (ref "D5") (pin "1") (pinfunction "K_1") (pintype "bidirectional"))
      (node (ref "EPD_C9") (pin "2") (pinfunction "2_2") (pintype "passive"))
      (node (ref "J1") (pin "21") (pinfunction "21_21") (pintype "bidirectional"))
    )
    (net (code "38") (name "PREVGL") (class "Default")
      (node (ref "D4") (pin "2") (pinfunction "A_2") (pintype "bidirectional"))
      (node (ref "EPD_C11") (pin "2") (pinfunction "2_2") (pintype "passive"))
      (node (ref "J1") (pin "23") (pinfunction "23_23") (pintype "bidirectional"))
    )
    (net (code "39") (name "RESE") (class "Default")
      (node (ref "J1") (pin "3") (pinfunction "3_3") (pintype "bidirectional"))
      (node (ref "Q4") (pin "2") (pinfunction "S_2") (pintype "bidirectional"))
      (node (ref "R2") (pin "1") (pinfunction "1_1") (pintype "passive"))
    )
    (net (code "40") (name "RESE'") (class "Default")
      (node (ref "R2") (pin "2") (pinfunction "2_2") (pintype "passive"))
      (node (ref "R4") (pin "2") (pinfunction "2_2") (pintype "passive"))
      (node (ref "SJ1") (pin "2") (pinfunction "2_2") (pintype "passive"))
    )
    (net (code "41") (name "RESET") (class "Default")
      (node (ref "C5") (pin "1") (pinfunction "1_1") (pintype "passive"))
      (node (ref "IC2") (pin "1") (pinfunction "VOUT_1") (pintype "bidirectional"))
      (node (ref "RESET_BUTTON") (pin "3") (pinfunction "3_3") (pintype "passive"))
      (node (ref "RESET_BUTTON") (pin "4") (pinfunction "4_4") (pintype "passive"))
      (node (ref "R_RESET") (pin "2") (pinfunction "2_2") (pintype "passive"))
      (node (ref "U1") (pin "3") (pinfunction "EN_3") (pintype "input"))
    )
    (net (code "42") (name "RTC_RST") (class "Default")
      (node (ref "U1") (pin "16") (pinfunction "IO18_16") (pintype "bidirectional"))
      (node (ref "U3") (pin "4") (pinfunction "~{RST}_4") (pintype "input"))
    )
    (net (code "43") (name "RX") (class "Default")
      (node (ref "RX") (pin "TP") (pinfunction "TP_TP") (pintype "input"))
      (node (ref "U1") (pin "24") (pinfunction "RXD0/GPIO17_24") (pintype "bidirectional"))
    )
    (net (code "44") (name "SCK") (class "Default")
      (node (ref "D8") (pin "2") (pinfunction "2_2") (pintype "passive"))
      (node (ref "J1") (pin "13") (pinfunction "13_13") (pintype "bidirectional"))
      (node (ref "J4") (pin "P5") (pinfunction "CLK_P5") (pintype "bidirectional"))
      (node (ref "R7") (pin "1") (pinfunction "1_1") (pintype "passive"))
      (node (ref "SCK") (pin "TP") (pinfunction "TP_TP") (pintype "input"))
      (node (ref "U1") (pin "6") (pinfunction "IO6_6") (pintype "bidirectional"))
      (node (ref "U2") (pin "6") (pinfunction "CLK_6") (pintype "input"))
    )
    (net (code "45") (name "SCL") (class "Default")
      (node (ref "J3") (pin "4") (pinfunction "4_4") (pintype "passive"))
      (node (ref "R2_PINH") (pin "1") (pinfunction "1_1") (pintype "passive"))
      (node (ref "SENSOR2") (pin "4") (pinfunction "SCK_4") (pintype "input"))
      (node (ref "U1") (pin "20") (pinfunction "IO22_20") (pintype "bidirectional"))
      (node (ref "U3") (pin "16") (pinfunction "SCL_16") (pintype "input"))
      (node (ref "U4") (pin "7") (pinfunction "SCL_7") (pintype "input"))
    )
    (net (code "46") (name "SDA") (class "Default")
      (node (ref "J3") (pin "3") (pinfunction "3_3") (pintype "passive"))
      (node (ref "R1_PINH") (pin "1") (pinfunction "1_1") (pintype "passive"))
      (node (ref "SENSOR2") (pin "3") (pinfunction "SDI_3") (pintype "bidirectional"))
      (node (ref "U1") (pin "19") (pinfunction "IO21_19") (pintype "bidirectional"))
      (node (ref "U3") (pin "15") (pinfunction "SDA_15") (pintype "bidirectional"))
      (node (ref "U4") (pin "8") (pinfunction "SDA_8") (pintype "bidirectional"))
    )
    (net (code "47") (name "SRC") (class "Default")
      (node (ref "C4") (pin "2") (pinfunction "2_2") (pintype "passive"))
      (node (ref "D5") (pin "2") (pinfunction "A_2") (pintype "bidirectional"))
      (node (ref "L1") (pin "1") (pinfunction "1_1") (pintype "passive"))
      (node (ref "Q4") (pin "3") (pinfunction "D_3") (pintype "bidirectional"))
    )
    (net (code "48") (name "SS_SD") (class "Default")
      (node (ref "D11") (pin "2") (pinfunction "2_2") (pintype "passive"))
      (node (ref "J4") (pin "P2") (pinfunction "CD/DAT3_P2") (pintype "bidirectional"))
      (node (ref "R10") (pin "1") (pinfunction "1_1") (pintype "passive"))
      (node (ref "U1") (pin "4") (pinfunction "IO4_4") (pintype "bidirectional"))
    )
    (net (code "49") (name "TX") (class "Default")
      (node (ref "TX") (pin "TP") (pinfunction "TP_TP") (pintype "input"))
      (node (ref "U1") (pin "25") (pinfunction "TXD0/GPIO16_25") (pintype "bidirectional"))
    )
    (net (code "50") (name "USB_D+") (class "Default")
      (node (ref "D1") (pin "4") (pinfunction "I/O2_2_4") (pintype "bidirectional"))
      (node (ref "U1") (pin "14") (pinfunction "IO13_14") (pintype "bidirectional"))
    )
    (net (code "51") (name "USB_D-") (class "Default")
      (node (ref "D1") (pin "6") (pinfunction "I/O1_2_6") (pintype "bidirectional"))
      (node (ref "U1") (pin "13") (pinfunction "IO12_13") (pintype "bidirectional"))
    )
    (net (code "52") (name "VBAT") (class "Default")
      (node (ref "C2_BAT") (pin "1") (pinfunction "1_1") (pintype "passive"))
      (node (ref "MCP73831") (pin "3") (pinfunction "VBAT_3") (pintype "power_in"))
      (node (ref "Q1") (pin "3") (pinfunction "D_3") (pintype "bidirectional"))
      (node (ref "U4") (pin "2") (pinfunction "CELL_2") (pintype "power_in"))
      (node (ref "U4") (pin "3") (pinfunction "VDD_3") (pintype "power_in"))
      (node (ref "VBAT") (pin "TP") (pinfunction "TP_TP") (pintype "input"))
    )
    (net (code "53") (name "VBUS") (class "Default")
      (node (ref "C1_BAT") (pin "1") (pinfunction "1_1") (pintype "passive"))
      (node (ref "C4_USB") (pin "1") (pinfunction "1_1") (pintype "passive"))
      (node (ref "C5_USB") (pin "1") (pinfunction "1_1") (pintype "passive"))
      (node (ref "CHG_LED") (pin "A") (pinfunction "A_A") (pintype "passive"))
      (node (ref "D1") (pin "2") (pinfunction "GND_2") (pintype "bidirectional"))
      (node (ref "D2") (pin "2") (pinfunction "ANODE_2") (pintype "bidirectional"))
      (node (ref "MCP73831") (pin "4") (pinfunction "VIN_4") (pintype "power_in"))
      (node (ref "PFMF.050.1") (pin "2") (pinfunction "2_2") (pintype "passive"))
      (node (ref "Q1") (pin "1") (pinfunction "G_1") (pintype "bidirectional"))
      (node (ref "R1_PWRUSB") (pin "2") (pinfunction "2_2") (pintype "passive"))
      (node (ref "VBUS") (pin "TP") (pinfunction "TP_TP") (pintype "input"))
    )
    (net (code "54") (name "VRTC") (class "Default")
      (node (ref "C1") (pin "1") (pinfunction "1_1") (pintype "passive"))
      (node (ref "C10_SUPERCAP") (pin "1") (pinfunction "1_1") (pintype "passive"))
      (node (ref "R_CAPACITOR") (pin "2") (pinfunction "2_2") (pintype "passive"))
      (node (ref "U3") (pin "14") (pinfunction "VBAT_14") (pintype "power_in"))
    )
    (net (code "55") (name "VUSB") (class "Default")
      (node (ref "J2") (pin "A4") (pinfunction "A4_A4") (pintype "bidirectional"))
      (node (ref "J2") (pin "A9") (pinfunction "A9_A9") (pintype "bidirectional"))
      (node (ref "J2") (pin "B4") (pinfunction "B4_B4") (pintype "bidirectional"))
      (node (ref "J2") (pin "B9") (pinfunction "B9_B9") (pintype "bidirectional"))
      (node (ref "PFMF.050.1") (pin "1") (pinfunction "1_1") (pintype "passive"))
    )
    (net (code "56") (name "unconnected-(IC1-NC-Pad4)") (class "Default")
      (node (ref "IC1") (pin "4") (pinfunction "NC_4") (pintype "no_connect"))
    )
    (net (code "57") (name "unconnected-(IC2-NC-Pad4)") (class "Default")
      (node (ref "IC2") (pin "4") (pinfunction "NC_4") (pintype "no_connect"))
    )
    (net (code "58") (name "unconnected-(J1-Pad1)") (class "Default")
      (node (ref "J1") (pin "1") (pinfunction "1_1") (pintype "bidirectional"))
    )
    (net (code "59") (name "unconnected-(J1-Pad6)") (class "Default")
      (node (ref "J1") (pin "6") (pinfunction "6_6") (pintype "bidirectional"))
    )
    (net (code "60") (name "unconnected-(J1-Pad7)") (class "Default")
      (node (ref "J1") (pin "7") (pinfunction "7_7") (pintype "bidirectional"))
    )
    (net (code "61") (name "unconnected-(J2-PadA8)") (class "Default")
      (node (ref "J2") (pin "A8") (pinfunction "A8_A8") (pintype "bidirectional"))
    )
    (net (code "62") (name "unconnected-(J2-PadB8)") (class "Default")
      (node (ref "J2") (pin "B8") (pinfunction "B8_B8") (pintype "bidirectional"))
    )
    (net (code "63") (name "unconnected-(J4-DAT1-PadP8)") (class "Default")
      (node (ref "J4") (pin "P8") (pinfunction "DAT1_P8") (pintype "bidirectional"))
    )
    (net (code "64") (name "unconnected-(J4-DAT2-PadP1)") (class "Default")
      (node (ref "J4") (pin "P1") (pinfunction "DAT2_P1") (pintype "bidirectional"))
    )
    (net (code "65") (name "unconnected-(J4-DETECTION_1-PadS1)") (class "Default")
      (node (ref "J4") (pin "S1") (pinfunction "DETECTION_1_S1") (pintype "bidirectional"))
    )
    (net (code "66") (name "unconnected-(J4-DETECTION_2-PadS2)") (class "Default")
      (node (ref "J4") (pin "S2") (pinfunction "DETECTION_2_S2") (pintype "bidirectional"))
    )
    (net (code "67") (name "unconnected-(U1-NC-Pad22)") (class "Default")
      (node (ref "U1") (pin "22") (pinfunction "NC_22") (pintype "no_connect"))
    )
    (net (code "68") (name "unconnected-(U4-~{ALERT}-Pad5)") (class "Default")
      (node (ref "U4") (pin "5") (pinfunction "~{ALERT}_5") (pintype "output"))
    )
  )
)
